# switchotron-3buttons-3lights-v1.net
KiCad netlist of a schematic drawn in EAGLE
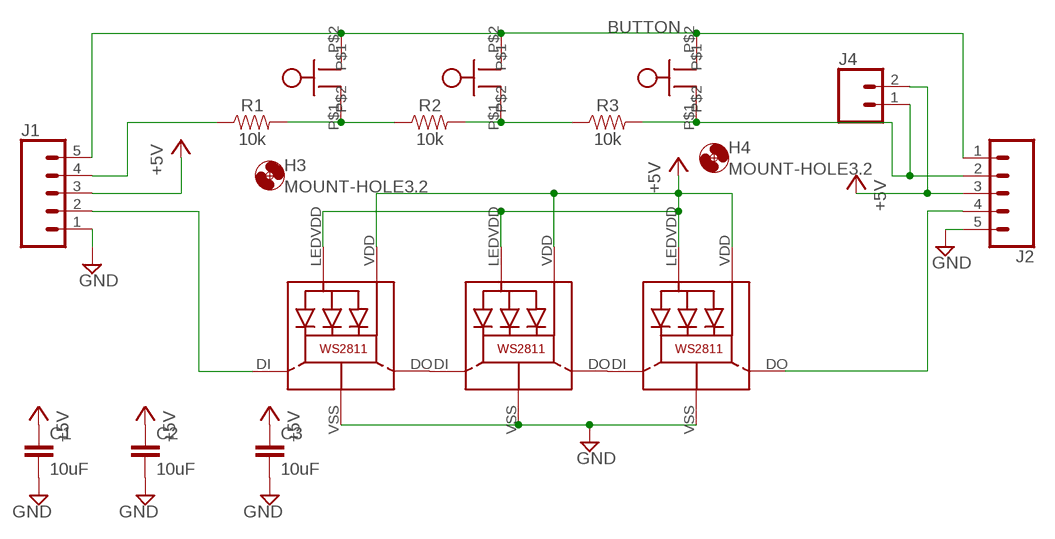
[diagram p0: schematic, sheet 1]

(export (version "E")
  (design (tool "Eeschema 10.0.6"))
  (components
    (comp (ref "C1")
      (value "10uF")
      (footprint "eagle-import:0603")
      (libsource (lib "eagle-import") (part "10UF-0603-6.3V-20%"))
    )
    (comp (ref "C2")
      (value "10uF")
      (footprint "eagle-import:0603")
      (libsource (lib "eagle-import") (part "10UF-0603-6.3V-20%"))
    )
    (comp (ref "C3")
      (value "10uF")
      (footprint "eagle-import:0603")
      (libsource (lib "eagle-import") (part "10UF-0603-6.3V-20%"))
    )
    (comp (ref "H3")
      (value "MOUNT-HOLE3.2")
      (footprint "eagle-import:3,2")
      (libsource (lib "eagle-import") (part "MOUNT-HOLE3.2"))
    )
    (comp (ref "H4")
      (value "MOUNT-HOLE3.2")
      (footprint "eagle-import:3,2")
      (libsource (lib "eagle-import") (part "MOUNT-HOLE3.2"))
    )
    (comp (ref "J1")
      (value "CONN_05")
      (footprint "eagle-import:1X05")
      (libsource (lib "eagle-import") (part "CONN_05"))
    )
    (comp (ref "J2")
      (value "CONN_05")
      (footprint "eagle-import:1X05")
      (libsource (lib "eagle-import") (part "CONN_05"))
    )
    (comp (ref "J4")
      (value "CONN_02")
      (footprint "eagle-import:1X02")
      (libsource (lib "eagle-import") (part "CONN_02"))
    )
    (comp (ref "LED1")
      (value "WS28115050")
      (footprint "eagle-import:WS28115050")
      (libsource (lib "eagle-import") (part "WS28115050"))
    )
    (comp (ref "LED2")
      (value "WS28115050")
      (footprint "eagle-import:WS28115050")
      (libsource (lib "eagle-import") (part "WS28115050"))
    )
    (comp (ref "LED8")
      (value "WS28115050")
      (footprint "eagle-import:WS28115050")
      (libsource (lib "eagle-import") (part "WS28115050"))
    )
    (comp (ref "R1")
      (value "10k")
      (footprint "eagle-import:0603")
      (libsource (lib "eagle-import") (part "10KOHM-0603-1/10W-1%"))
    )
    (comp (ref "R2")
      (value "10k")
      (footprint "eagle-import:0603")
      (libsource (lib "eagle-import") (part "10KOHM-0603-1/10W-1%"))
    )
    (comp (ref "R3")
      (value "10k")
      (footprint "eagle-import:0603")
      (libsource (lib "eagle-import") (part "10KOHM-0603-1/10W-1%"))
    )
    (comp (ref "U$1")
      (value "BUTTON")
      (footprint "eagle-import:BUTTON")
      (libsource (lib "eagle-import") (part "BUTTON"))
    )
    (comp (ref "U$4")
      (value "BUTTON")
      (footprint "eagle-import:BUTTON")
      (libsource (lib "eagle-import") (part "BUTTON"))
    )
    (comp (ref "U$5")
      (value "BUTTON")
      (footprint "eagle-import:BUTTON")
      (libsource (lib "eagle-import") (part "BUTTON"))
    )
  )
  (nets
    (net (code "1") (name "+5V") (class "Default")
      (node (ref "C1") (pin "1") (pinfunction "1_1") (pintype "passive"))
      (node (ref "C2") (pin "1") (pinfunction "1_1") (pintype "passive"))
      (node (ref "C3") (pin "1") (pinfunction "1_1") (pintype "passive"))
      (node (ref "J1") (pin "3") (pinfunction "3_3") (pintype "passive"))
      (node (ref "J2") (pin "3") (pinfunction "3_3") (pintype "passive"))
      (node (ref "J4") (pin "2") (pinfunction "2_2") (pintype "passive"))
      (node (ref "LED1") (pin "LEDVDD") (pinfunction "LEDVDD_LEDVDD") (pintype "power_in"))
      (node (ref "LED1") (pin "VDD") (pinfunction "VDD_VDD") (pintype "power_in"))
      (node (ref "LED2") (pin "LEDVDD") (pinfunction "LEDVDD_LEDVDD") (pintype "power_in"))
      (node (ref "LED2") (pin "VDD") (pinfunction "VDD_VDD") (pintype "power_in"))
      (node (ref "LED8") (pin "LEDVDD") (pinfunction "LEDVDD_LEDVDD") (pintype "power_in"))
      (node (ref "LED8") (pin "VDD") (pinfunction "VDD_VDD") (pintype "power_in"))
    )
    (net (code "2") (name "/BUTTON") (class "Default")
      (node (ref "J1") (pin "5") (pinfunction "5_5") (pintype "passive"))
      (node (ref "J2") (pin "1") (pinfunction "1_1") (pintype "passive"))
      (node (ref "U$1") (pin "P$2") (pinfunction "P$2_P$2") (pintype "bidirectional"))
      (node (ref "U$4") (pin "P$2") (pinfunction "P$2_P$2") (pintype "bidirectional"))
      (node (ref "U$5") (pin "P$2") (pinfunction "P$2_P$2") (pintype "bidirectional"))
    )
    (net (code "3") (name "GND") (class "Default")
      (node (ref "C1") (pin "2") (pinfunction "2_2") (pintype "passive"))
      (node (ref "C2") (pin "2") (pinfunction "2_2") (pintype "passive"))
      (node (ref "C3") (pin "2") (pinfunction "2_2") (pintype "passive"))
      (node (ref "J1") (pin "1") (pinfunction "1_1") (pintype "passive"))
      (node (ref "J2") (pin "5") (pinfunction "5_5") (pintype "passive"))
      (node (ref "LED1") (pin "VSS") (pinfunction "GND_VSS") (pintype "power_in"))
      (node (ref "LED2") (pin "VSS") (pinfunction "GND_VSS") (pintype "power_in"))
      (node (ref "LED8") (pin "VSS") (pinfunction "GND_VSS") (pintype "power_in"))
    )
    (net (code "4") (name "Net-(J1-Pad2)") (class "Default")
      (node (ref "J1") (pin "2") (pinfunction "2_2") (pintype "passive"))
      (node (ref "LED1") (pin "DI") (pinfunction "DI_DI") (pintype "input"))
    )
    (net (code "5") (name "Net-(J1-Pad4)") (class "Default")
      (node (ref "J1") (pin "4") (pinfunction "4_4") (pintype "passive"))
      (node (ref "R1") (pin "1") (pinfunction "1_1") (pintype "passive"))
    )
    (net (code "6") (name "Net-(J2-Pad2)") (class "Default")
      (node (ref "J2") (pin "2") (pinfunction "2_2") (pintype "passive"))
      (node (ref "J4") (pin "1") (pinfunction "1_1") (pintype "passive"))
      (node (ref "R3") (pin "2") (pinfunction "2_2") (pintype "passive"))
      (node (ref "U$5") (pin "P$1") (pinfunction "P$1_P$1") (pintype "bidirectional"))
    )
    (net (code "7") (name "Net-(J2-Pad4)") (class "Default")
      (node (ref "J2") (pin "4") (pinfunction "4_4") (pintype "passive"))
      (node (ref "LED8") (pin "DO") (pinfunction "DO_DO") (pintype "output"))
    )
    (net (code "8") (name "Net-(LED1-PadDO)") (class "Default")
      (node (ref "LED1") (pin "DO") (pinfunction "DO_DO") (pintype "output"))
      (node (ref "LED2") (pin "DI") (pinfunction "DI_DI") (pintype "input"))
    )
    (net (code "9") (name "Net-(LED2-PadDO)") (class "Default")
      (node (ref "LED2") (pin "DO") (pinfunction "DO_DO") (pintype "output"))
      (node (ref "LED8") (pin "DI") (pinfunction "DI_DI") (pintype "input"))
    )
    (net (code "10") (name "Net-(R1-Pad2)") (class "Default")
      (node (ref "R1") (pin "2") (pinfunction "2_2") (pintype "passive"))
      (node (ref "R2") (pin "1") (pinfunction "1_1") (pintype "passive"))
      (node (ref "U$1") (pin "P$1") (pinfunction "P$1_P$1") (pintype "bidirectional"))
    )
    (net (code "11") (name "Net-(R2-Pad2)") (class "Default")
      (node (ref "R2") (pin "2") (pinfunction "2_2") (pintype "passive"))
      (node (ref "R3") (pin "1") (pinfunction "1_1") (pintype "passive"))
      (node (ref "U$4") (pin "P$1") (pinfunction "P$1_P$1") (pintype "bidirectional"))
    )
  )
)
